# LED_CONTROLLER.net
KiCad netlist of a schematic drawn in Altium Designer
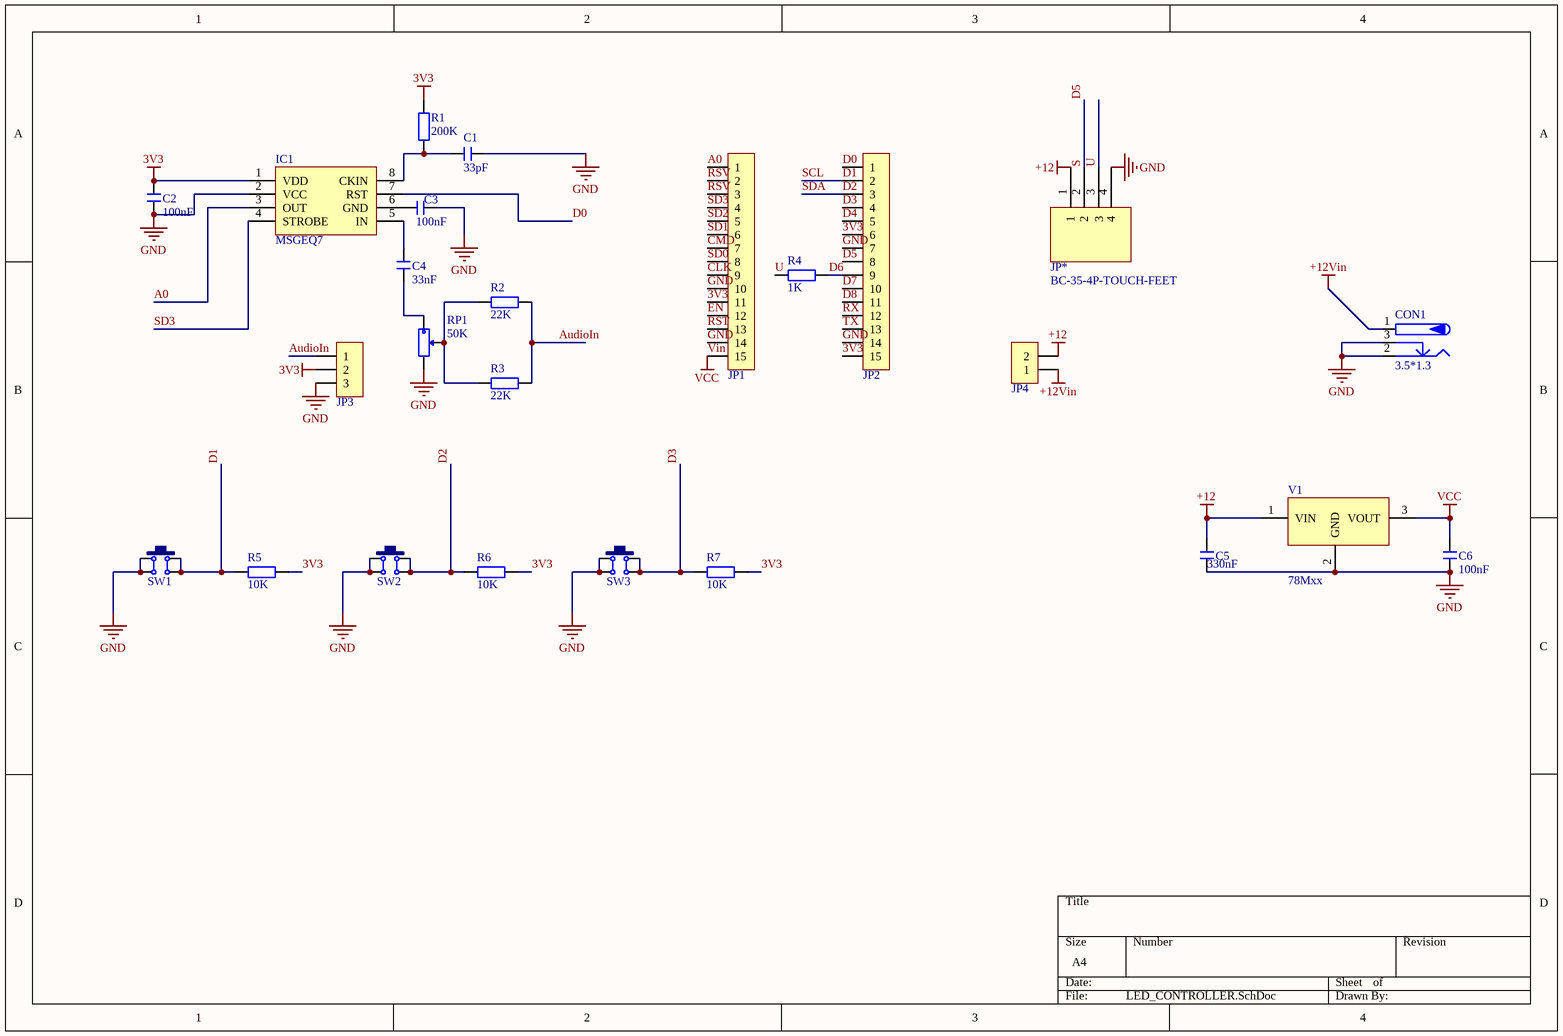
[diagram p0: LED_CONTROLLER.SchDoc]

(export (version "E")
  (design (tool "Eeschema 10.0.6"))
  (components
    (comp (ref "C1")
      (value "33pF")
      (footprint "C 0603_L")
      (description "无极性贴片电容")
      (fields (field (name "版权归属") "源创客"))
      (libsource (lib "3.1   - 电阻-电容-电感") (part "C"))
    )
    (comp (ref "C2")
      (value "100nF")
      (footprint "C 0603_L")
      (description "无极性贴片电容")
      (fields (field (name "版权归属") "源创客"))
      (libsource (lib "3.1   - 电阻-电容-电感") (part "C"))
    )
    (comp (ref "C3")
      (value "100nF")
      (footprint "C 0603_L")
      (description "无极性贴片电容")
      (fields (field (name "版权归属") "源创客"))
      (libsource (lib "3.1   - 电阻-电容-电感") (part "C"))
    )
    (comp (ref "C4")
      (value "33nF")
      (footprint "C 0603_L")
      (description "无极性贴片电容")
      (fields (field (name "版权归属") "源创客"))
      (libsource (lib "3.1   - 电阻-电容-电感") (part "C"))
    )
    (comp (ref "C5")
      (value "330nF")
      (footprint "C 0603_L")
      (description "无极性贴片电容")
      (fields (field (name "版权归属") "源创客"))
      (libsource (lib "3.1   - 电阻-电容-电感") (part "C"))
    )
    (comp (ref "C6")
      (value "100nF")
      (footprint "C 0603_L")
      (description "无极性贴片电容")
      (fields (field (name "版权归属") "源创客"))
      (libsource (lib "3.1   - 电阻-电容-电感") (part "C"))
    )
    (comp (ref "CON1")
      (value "3.5*1.3")
      (footprint "DC-050")
      (description "低压电源接口")
      (fields (field (name "版权归属") "源创客"))
      (libsource (lib "4.1   - 接口类") (part "P-DC"))
    )
    (comp (ref "IC1")
      (value "MSGEQ7")
      (footprint "DIP8-300")
      (fields (field (name "版权归属") "源创客"))
      (libsource (lib "1.1   - IC芯片") (part "MSGEQ7"))
    )
    (comp (ref "JP*")
      (value "BC-35-4P-TOUCH-FEET")
      (footprint "BC-35-4P-TOUCH-FEET")
      (libsource (lib "15.1 - 未分类器件") (part "BC-35-4P-TOUCH-FEET"))
    )
    (comp (ref "JP1")
      (value "HDR-1X15")
      (footprint "HDR2.54-M-LI-15P")
      (description "15P接插件")
      (fields (field (name "版权归属") "源创客"))
      (libsource (lib "4.6   - 接插件-脚距2.54") (part "Header 15"))
    )
    (comp (ref "JP2")
      (value "HDR-1X15")
      (footprint "HDR2.54-M-LI-15P")
      (description "15P接插件")
      (fields (field (name "版权归属") "源创客"))
      (libsource (lib "4.6   - 接插件-脚距2.54") (part "Header 15"))
    )
    (comp (ref "JP3")
      (value "HDR-1X3")
      (footprint "HDR2.54-M-LI-3P")
      (description "3P接插件")
      (fields (field (name "版权归属") "源创客"))
      (libsource (lib "4.6   - 接插件-脚距2.54") (part "Header 3"))
    )
    (comp (ref "JP4")
      (value "HDR-1X2")
      (footprint "KF128-3.81-2P")
      (description "2P接插件")
      (fields (field (name "版权归属") "源创客"))
      (libsource (lib "4.8   - 接插件-脚距3.81") (part "Header 2"))
    )
    (comp (ref "R1")
      (value "200K")
      (footprint "R 0603_L")
      (description "贴片电阻")
      (fields (field (name "版权归属") "源创客"))
      (libsource (lib "3.1   - 电阻-电容-电感") (part "R"))
    )
    (comp (ref "R2")
      (value "22K")
      (footprint "R 0603_L")
      (description "贴片电阻")
      (fields (field (name "版权归属") "源创客"))
      (libsource (lib "3.1   - 电阻-电容-电感") (part "R"))
    )
    (comp (ref "R3")
      (value "22K")
      (footprint "R 0603_L")
      (description "贴片电阻")
      (fields (field (name "版权归属") "源创客"))
      (libsource (lib "3.1   - 电阻-电容-电感") (part "R"))
    )
    (comp (ref "R4")
      (value "1K")
      (footprint "R 0603_L")
      (description "贴片电阻")
      (fields (field (name "版权归属") "源创客"))
      (libsource (lib "3.1   - 电阻-电容-电感") (part "R"))
    )
    (comp (ref "R5")
      (value "10K")
      (footprint "R 0603_L")
      (description "贴片电阻")
      (fields (field (name "版权归属") "源创客"))
      (libsource (lib "3.1   - 电阻-电容-电感") (part "R"))
    )
    (comp (ref "R6")
      (value "10K")
      (footprint "R 0603_L")
      (description "贴片电阻")
      (fields (field (name "版权归属") "源创客"))
      (libsource (lib "3.1   - 电阻-电容-电感") (part "R"))
    )
    (comp (ref "R7")
      (value "10K")
      (footprint "R 0603_L")
      (description "贴片电阻")
      (fields (field (name "版权归属") "源创客"))
      (libsource (lib "3.1   - 电阻-电容-电感") (part "R"))
    )
    (comp (ref "RP1")
      (value "50K")
      (footprint "3362P")
      (description "插件单联电位器")
      (fields (field (name "版权归属") "源创客"))
      (libsource (lib "3.1   - 电阻-电容-电感") (part "RP-ID"))
    )
    (comp (ref "SW1")
      (value "6x6x5")
      (footprint "TSW SMD-6*6*15")
      (description "贴片6x6轻触开关")
      (fields (field (name "版权归属") "源创客"))
      (libsource (lib "5.1   - 按键-开关") (part "TSW SMD-6x6"))
    )
    (comp (ref "SW2")
      (value "6x6x5")
      (footprint "TSW SMD-6*6*15")
      (description "贴片6x6轻触开关")
      (fields (field (name "版权归属") "源创客"))
      (libsource (lib "5.1   - 按键-开关") (part "TSW SMD-6x6"))
    )
    (comp (ref "SW3")
      (value "6x6x5")
      (footprint "TSW SMD-6*6*15")
      (description "贴片6x6轻触开关")
      (fields (field (name "版权归属") "源创客"))
      (libsource (lib "5.1   - 按键-开关") (part "TSW SMD-6x6"))
    )
    (comp (ref "V1")
      (value "78Mxx")
      (footprint "TO252")
      (description "线性稳压芯片")
      (fields (field (name "版权归属") "源创客"))
      (libsource (lib "1.3   - 电源类芯片") (part "78Mxx"))
    )
  )
  (nets
    (net (code "1") (name "+12") (class "Default")
      (node (ref "C5") (pin "1") (pinfunction "1_1") (pintype "passive"))
      (node (ref "JP*") (pin "1") (pinfunction "1_1") (pintype "passive"))
      (node (ref "JP4") (pin "2") (pinfunction "2_2") (pintype "passive"))
      (node (ref "V1") (pin "1") (pinfunction "VIN_1") (pintype "passive"))
    )
    (net (code "2") (name "+12Vin") (class "Default")
      (node (ref "CON1") (pin "1") (pintype "power_in"))
      (node (ref "JP4") (pin "1") (pinfunction "1_1") (pintype "passive"))
    )
    (net (code "3") (name "/A0") (class "Default")
      (node (ref "IC1") (pin "3") (pinfunction "OUT_3") (pintype "passive"))
      (node (ref "JP1") (pin "1") (pinfunction "1_1") (pintype "passive"))
    )
    (net (code "4") (name "/AudioIn") (class "Default")
      (node (ref "JP3") (pin "1") (pinfunction "1_1") (pintype "passive"))
      (node (ref "R2") (pin "2") (pinfunction "2_2") (pintype "passive"))
      (node (ref "R3") (pin "2") (pinfunction "2_2") (pintype "passive"))
    )
    (net (code "5") (name "/CLK") (class "Default")
      (node (ref "JP1") (pin "9") (pinfunction "9_9") (pintype "passive"))
    )
    (net (code "6") (name "/CMD") (class "Default")
      (node (ref "JP1") (pin "7") (pinfunction "7_7") (pintype "passive"))
    )
    (net (code "7") (name "/D0") (class "Default")
      (node (ref "IC1") (pin "7") (pinfunction "RST_7") (pintype "passive"))
      (node (ref "JP2") (pin "1") (pinfunction "1_1") (pintype "passive"))
    )
    (net (code "8") (name "/D1") (class "Default")
      (node (ref "JP2") (pin "2") (pinfunction "2_2") (pintype "passive"))
      (node (ref "R5") (pin "1") (pinfunction "1_1") (pintype "passive"))
      (node (ref "SW1") (pin "2") (pinfunction "2_2") (pintype "passive"))
      (node (ref "SW1") (pin "3") (pinfunction "3_3") (pintype "passive"))
    )
    (net (code "9") (name "/D2") (class "Default")
      (node (ref "JP2") (pin "3") (pinfunction "3_3") (pintype "passive"))
      (node (ref "R6") (pin "1") (pinfunction "1_1") (pintype "passive"))
      (node (ref "SW2") (pin "2") (pinfunction "2_2") (pintype "passive"))
      (node (ref "SW2") (pin "3") (pinfunction "3_3") (pintype "passive"))
    )
    (net (code "10") (name "/D3") (class "Default")
      (node (ref "JP2") (pin "4") (pinfunction "4_4") (pintype "passive"))
      (node (ref "R7") (pin "1") (pinfunction "1_1") (pintype "passive"))
      (node (ref "SW3") (pin "2") (pinfunction "2_2") (pintype "passive"))
      (node (ref "SW3") (pin "3") (pinfunction "3_3") (pintype "passive"))
    )
    (net (code "11") (name "/D4") (class "Default")
      (node (ref "JP2") (pin "5") (pinfunction "5_5") (pintype "passive"))
    )
    (net (code "12") (name "/D5") (class "Default")
      (node (ref "JP*") (pin "2") (pinfunction "2_2") (pintype "passive"))
      (node (ref "JP2") (pin "8") (pinfunction "8_8") (pintype "passive"))
    )
    (net (code "13") (name "/D6") (class "Default")
      (node (ref "JP2") (pin "9") (pinfunction "9_9") (pintype "passive"))
      (node (ref "R4") (pin "1") (pinfunction "1_1") (pintype "passive"))
    )
    (net (code "14") (name "/D7") (class "Default")
      (node (ref "JP2") (pin "10") (pinfunction "10_10") (pintype "passive"))
    )
    (net (code "15") (name "/D8") (class "Default")
      (node (ref "JP2") (pin "11") (pinfunction "11_11") (pintype "passive"))
    )
    (net (code "16") (name "/EN") (class "Default")
      (node (ref "JP1") (pin "12") (pinfunction "12_12") (pintype "passive"))
    )
    (net (code "17") (name "/RST") (class "Default")
      (node (ref "JP1") (pin "13") (pinfunction "13_13") (pintype "passive"))
    )
    (net (code "18") (name "/RSV") (class "Default")
      (node (ref "JP1") (pin "2") (pinfunction "2_2") (pintype "passive"))
      (node (ref "JP1") (pin "3") (pinfunction "3_3") (pintype "passive"))
    )
    (net (code "19") (name "/RX") (class "Default")
      (node (ref "JP2") (pin "12") (pinfunction "12_12") (pintype "passive"))
    )
    (net (code "20") (name "/SD0") (class "Default")
      (node (ref "JP1") (pin "8") (pinfunction "8_8") (pintype "passive"))
    )
    (net (code "21") (name "/SD1") (class "Default")
      (node (ref "JP1") (pin "6") (pinfunction "6_6") (pintype "passive"))
    )
    (net (code "22") (name "/SD2") (class "Default")
      (node (ref "JP1") (pin "5") (pinfunction "5_5") (pintype "passive"))
    )
    (net (code "23") (name "/SD3") (class "Default")
      (node (ref "IC1") (pin "4") (pinfunction "STROBE_4") (pintype "passive"))
      (node (ref "JP1") (pin "4") (pinfunction "4_4") (pintype "passive"))
    )
    (net (code "24") (name "/TX") (class "Default")
      (node (ref "JP2") (pin "13") (pinfunction "13_13") (pintype "passive"))
    )
    (net (code "25") (name "/U") (class "Default")
      (node (ref "JP*") (pin "3") (pinfunction "3_3") (pintype "passive"))
      (node (ref "R4") (pin "2") (pinfunction "2_2") (pintype "passive"))
    )
    (net (code "26") (name "3V3") (class "Default")
      (node (ref "C2") (pin "2") (pinfunction "2_2") (pintype "passive"))
      (node (ref "IC1") (pin "1") (pinfunction "VDD_1") (pintype "passive"))
      (node (ref "JP1") (pin "11") (pinfunction "11_11") (pintype "passive"))
      (node (ref "JP2") (pin "15") (pinfunction "15_15") (pintype "passive"))
      (node (ref "JP2") (pin "6") (pinfunction "6_6") (pintype "passive"))
      (node (ref "JP3") (pin "2") (pinfunction "2_2") (pintype "passive"))
      (node (ref "R1") (pin "2") (pinfunction "2_2") (pintype "passive"))
      (node (ref "R5") (pin "2") (pinfunction "2_2") (pintype "passive"))
      (node (ref "R6") (pin "2") (pinfunction "2_2") (pintype "passive"))
      (node (ref "R7") (pin "2") (pinfunction "2_2") (pintype "passive"))
    )
    (net (code "27") (name "GND") (class "Default")
      (node (ref "C1") (pin "1") (pinfunction "1_1") (pintype "passive"))
      (node (ref "C2") (pin "1") (pinfunction "1_1") (pintype "passive"))
      (node (ref "C3") (pin "1") (pinfunction "1_1") (pintype "passive"))
      (node (ref "C5") (pin "2") (pinfunction "2_2") (pintype "passive"))
      (node (ref "C6") (pin "1") (pinfunction "1_1") (pintype "passive"))
      (node (ref "CON1") (pin "2") (pintype "power_in"))
      (node (ref "CON1") (pin "3") (pintype "power_in"))
      (node (ref "IC1") (pin "2") (pinfunction "VCC_2") (pintype "passive"))
      (node (ref "JP*") (pin "4") (pinfunction "4_4") (pintype "passive"))
      (node (ref "JP1") (pin "10") (pinfunction "10_10") (pintype "passive"))
      (node (ref "JP1") (pin "14") (pinfunction "14_14") (pintype "passive"))
      (node (ref "JP2") (pin "14") (pinfunction "14_14") (pintype "passive"))
      (node (ref "JP2") (pin "7") (pinfunction "7_7") (pintype "passive"))
      (node (ref "JP3") (pin "3") (pinfunction "3_3") (pintype "passive"))
      (node (ref "RP1") (pin "3") (pinfunction "3_3") (pintype "passive"))
      (node (ref "SW1") (pin "1") (pinfunction "1_1") (pintype "passive"))
      (node (ref "SW1") (pin "4") (pinfunction "4_4") (pintype "passive"))
      (node (ref "SW2") (pin "1") (pinfunction "1_1") (pintype "passive"))
      (node (ref "SW2") (pin "4") (pinfunction "4_4") (pintype "passive"))
      (node (ref "SW3") (pin "1") (pinfunction "1_1") (pintype "passive"))
      (node (ref "SW3") (pin "4") (pinfunction "4_4") (pintype "passive"))
      (node (ref "V1") (pin "2") (pinfunction "GND_2") (pintype "passive"))
    )
    (net (code "28") (name "Net-(C4-Pad1)") (class "Default")
      (node (ref "C4") (pin "1") (pinfunction "1_1") (pintype "passive"))
      (node (ref "RP1") (pin "1") (pinfunction "1_1") (pintype "passive"))
    )
    (net (code "29") (name "Net-(IC1-CKIN)") (class "Default")
      (node (ref "C1") (pin "2") (pinfunction "2_2") (pintype "passive"))
      (node (ref "IC1") (pin "8") (pinfunction "CKIN_8") (pintype "passive"))
      (node (ref "R1") (pin "1") (pinfunction "1_1") (pintype "passive"))
    )
    (net (code "30") (name "Net-(IC1-GND)") (class "Default")
      (node (ref "C3") (pin "2") (pinfunction "2_2") (pintype "passive"))
      (node (ref "IC1") (pin "6") (pinfunction "GND_6") (pintype "passive"))
    )
    (net (code "31") (name "Net-(IC1-IN)") (class "Default")
      (node (ref "C4") (pin "2") (pinfunction "2_2") (pintype "passive"))
      (node (ref "IC1") (pin "5") (pinfunction "IN_5") (pintype "passive"))
    )
    (net (code "32") (name "Net-(R2-Pad1)") (class "Default")
      (node (ref "R2") (pin "1") (pinfunction "1_1") (pintype "passive"))
      (node (ref "R3") (pin "1") (pinfunction "1_1") (pintype "passive"))
      (node (ref "RP1") (pin "2") (pinfunction "2_2") (pintype "passive"))
    )
    (net (code "33") (name "VCC") (class "Default")
      (node (ref "C6") (pin "2") (pinfunction "2_2") (pintype "passive"))
      (node (ref "JP1") (pin "15") (pinfunction "15_15") (pintype "passive"))
      (node (ref "V1") (pin "3") (pinfunction "VOUT_3") (pintype "passive"))
    )
  )
)
